# CAN1.net
KiCad netlist of a schematic drawn in Altium Designer
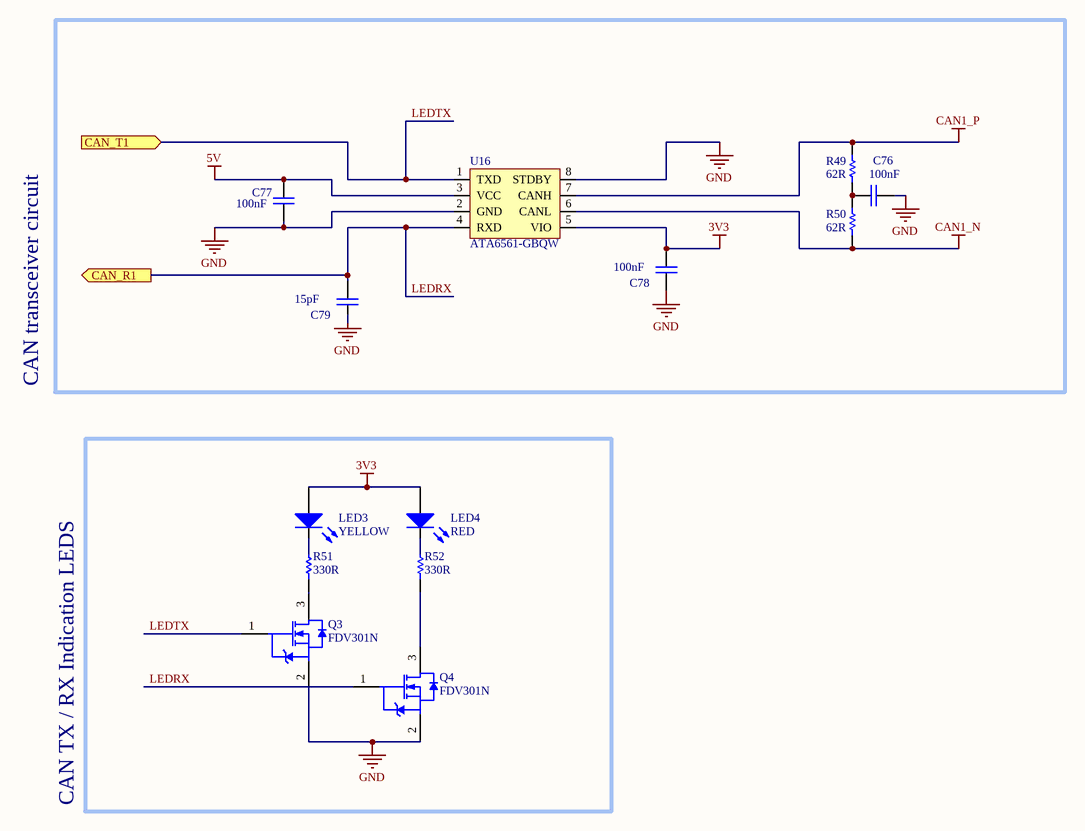
[diagram p0: CAN1.SchDoc]

(export (version "E")
  (design (tool "Eeschema 10.0.6"))
  (components
    (comp (ref "C76")
      (value "100nF")
      (footprint "C1206")
      (description "C1206")
      (fields (field (name "Comment") "C1206C106K3PACTU"))
      (libsource (lib "Passive components") (part "C1206C106K3PACTU"))
    )
    (comp (ref "C77")
      (value "100nF")
      (footprint "C1206")
      (description "C1206")
      (fields (field (name "Comment") "C1206C106K3PACTU"))
      (libsource (lib "Passive components") (part "C1206C106K3PACTU"))
    )
    (comp (ref "C78")
      (value "100nF")
      (footprint "C1206")
      (description "C1206")
      (fields (field (name "Comment") "C1206C106K3PACTU"))
      (libsource (lib "Passive components") (part "C1206C106K3PACTU"))
    )
    (comp (ref "C79")
      (value "15pF")
      (footprint "C1206")
      (description "C1206")
      (fields (field (name "Comment") "C1206C106K3PACTU"))
      (libsource (lib "Passive components") (part "C1206C106K3PACTU"))
    )
    (comp (ref "LED3")
      (value "YELLOW")
      (footprint "0603_A")
      (description "SMD mono-color Chip LED, WL-SMCW, Red")
      (fields (field (name "MANUFACTURER") "Wuerth Elektronik") (field (name "PARTNUMBER") "150060RS75000"))
      (libsource (lib "Altium Content Vault") (part "WE-LED_K1A2-2"))
    )
    (comp (ref "LED4")
      (value "RED")
      (footprint "0603_A")
      (description "SMD mono-color Chip LED, WL-SMCW, Red")
      (fields (field (name "MANUFACTURER") "Wuerth Elektronik") (field (name "PARTNUMBER") "150060RS75000"))
      (libsource (lib "Altium Content Vault") (part "WE-LED_K1A2-2"))
    )
    (comp (ref "Q3")
      (value "FDV301N")
      (footprint "FAIR-SOT23-3_V")
      (description "Digital FET, N-Channel, 0.35 W, 25 V, -55 to 150 degC, 3-Pin SOT23, RoHS, Tape and Reel")
      (fields (field (name "MANUFACTURER") "Fairchild"))
      (libsource (lib "Altium Content Vault") (part "NEMOS-GSD-3_D"))
    )
    (comp (ref "Q4")
      (value "FDV301N")
      (footprint "FAIR-SOT23-3_V")
      (description "Digital FET, N-Channel, 0.35 W, 25 V, -55 to 150 degC, 3-Pin SOT23, RoHS, Tape and Reel")
      (fields (field (name "MANUFACTURER") "Fairchild"))
      (libsource (lib "Altium Content Vault") (part "NEMOS-GSD-3_D"))
    )
    (comp (ref "R49")
      (value "62R")
      (footprint "RESC0603(1608)_L")
      (description "330R 0.1W 5% 0603 (1608 Metric)  SMD")
      (fields (field (name "TOLERANCE") "5 %") (field (name "POWER") "0.1 W"))
      (libsource (lib "Altium Content Vault") (part "RES"))
    )
    (comp (ref "R50")
      (value "62R")
      (footprint "RESC0603(1608)_L")
      (description "330R 0.1W 5% 0603 (1608 Metric)  SMD")
      (fields (field (name "TOLERANCE") "5 %") (field (name "POWER") "0.1 W"))
      (libsource (lib "Altium Content Vault") (part "RES"))
    )
    (comp (ref "R51")
      (value "330R")
      (footprint "RESC0603(1608)_L")
      (description "330R 0.1W 5% 0603 (1608 Metric)  SMD")
      (fields (field (name "TOLERANCE") "5 %") (field (name "POWER") "0.1 W"))
      (libsource (lib "Altium Content Vault") (part "RES"))
    )
    (comp (ref "R52")
      (value "330R")
      (footprint "RESC0603(1608)_L")
      (description "330R 0.1W 5% 0603 (1608 Metric)  SMD")
      (fields (field (name "TOLERANCE") "5 %") (field (name "POWER") "0.1 W"))
      (libsource (lib "Altium Content Vault") (part "RES"))
    )
    (comp (ref "U16")
      (value "ATA6561-GBQW")
      (footprint "LME49721MA/NOPB")
      (libsource (lib "IC") (part "ATA6561-GBQW"))
    )
  )
  (nets
    (net (code "1") (name "/LEDRX") (class "Default")
      (node (ref "C79") (pin "2") (pinfunction "2_2") (pintype "passive"))
      (node (ref "Q4") (pin "1") (pinfunction "G_1") (pintype "passive"))
      (node (ref "U16") (pin "4") (pinfunction "RXD_4") (pintype "passive"))
    )
    (net (code "2") (name "/LEDTX") (class "Default")
      (node (ref "Q3") (pin "1") (pinfunction "G_1") (pintype "passive"))
      (node (ref "U16") (pin "1") (pinfunction "TXD_1") (pintype "passive"))
    )
    (net (code "3") (name "3V3") (class "Default")
      (node (ref "C78") (pin "2") (pinfunction "2_2") (pintype "passive"))
      (node (ref "LED3") (pin "2") (pinfunction "A_2") (pintype "passive"))
      (node (ref "LED4") (pin "2") (pinfunction "A_2") (pintype "passive"))
      (node (ref "U16") (pin "5") (pinfunction "VIO_5") (pintype "passive"))
    )
    (net (code "4") (name "5V") (class "Default")
      (node (ref "C77") (pin "2") (pinfunction "2_2") (pintype "passive"))
      (node (ref "U16") (pin "3") (pinfunction "VCC_3") (pintype "passive"))
    )
    (net (code "5") (name "CAN1_N") (class "Default")
      (node (ref "R50") (pin "2") (pinfunction "2_2") (pintype "passive"))
      (node (ref "U16") (pin "6") (pinfunction "CANL_6") (pintype "passive"))
    )
    (net (code "6") (name "CAN1_P") (class "Default")
      (node (ref "R49") (pin "1") (pinfunction "1_1") (pintype "passive"))
      (node (ref "U16") (pin "7") (pinfunction "CANH_7") (pintype "passive"))
    )
    (net (code "7") (name "GND") (class "Default")
      (node (ref "C76") (pin "1") (pinfunction "1_1") (pintype "passive"))
      (node (ref "C77") (pin "1") (pinfunction "1_1") (pintype "passive"))
      (node (ref "C78") (pin "1") (pinfunction "1_1") (pintype "passive"))
      (node (ref "C79") (pin "1") (pinfunction "1_1") (pintype "passive"))
      (node (ref "Q3") (pin "2") (pinfunction "S_2") (pintype "passive"))
      (node (ref "Q4") (pin "2") (pinfunction "S_2") (pintype "passive"))
      (node (ref "U16") (pin "2") (pinfunction "GND_2") (pintype "passive"))
      (node (ref "U16") (pin "8") (pinfunction "STDBY_8") (pintype "passive"))
    )
    (net (code "8") (name "Net-(C76-Pad2)") (class "Default")
      (node (ref "C76") (pin "2") (pinfunction "2_2") (pintype "passive"))
      (node (ref "R49") (pin "2") (pinfunction "2_2") (pintype "passive"))
      (node (ref "R50") (pin "1") (pinfunction "1_1") (pintype "passive"))
    )
    (net (code "9") (name "Net-(LED3-K)") (class "Default")
      (node (ref "LED3") (pin "1") (pinfunction "K_1") (pintype "passive"))
      (node (ref "R51") (pin "1") (pinfunction "1_1") (pintype "passive"))
    )
    (net (code "10") (name "Net-(LED4-K)") (class "Default")
      (node (ref "LED4") (pin "1") (pinfunction "K_1") (pintype "passive"))
      (node (ref "R52") (pin "1") (pinfunction "1_1") (pintype "passive"))
    )
    (net (code "11") (name "Net-(Q3-D)") (class "Default")
      (node (ref "Q3") (pin "3") (pinfunction "D_3") (pintype "passive"))
      (node (ref "R51") (pin "2") (pinfunction "2_2") (pintype "passive"))
    )
    (net (code "12") (name "Net-(Q4-D)") (class "Default")
      (node (ref "Q4") (pin "3") (pinfunction "D_3") (pintype "passive"))
      (node (ref "R52") (pin "2") (pinfunction "2_2") (pintype "passive"))
    )
  )
)
